# PID_interface_01.net
KiCad netlist of a schematic drawn in EAGLE
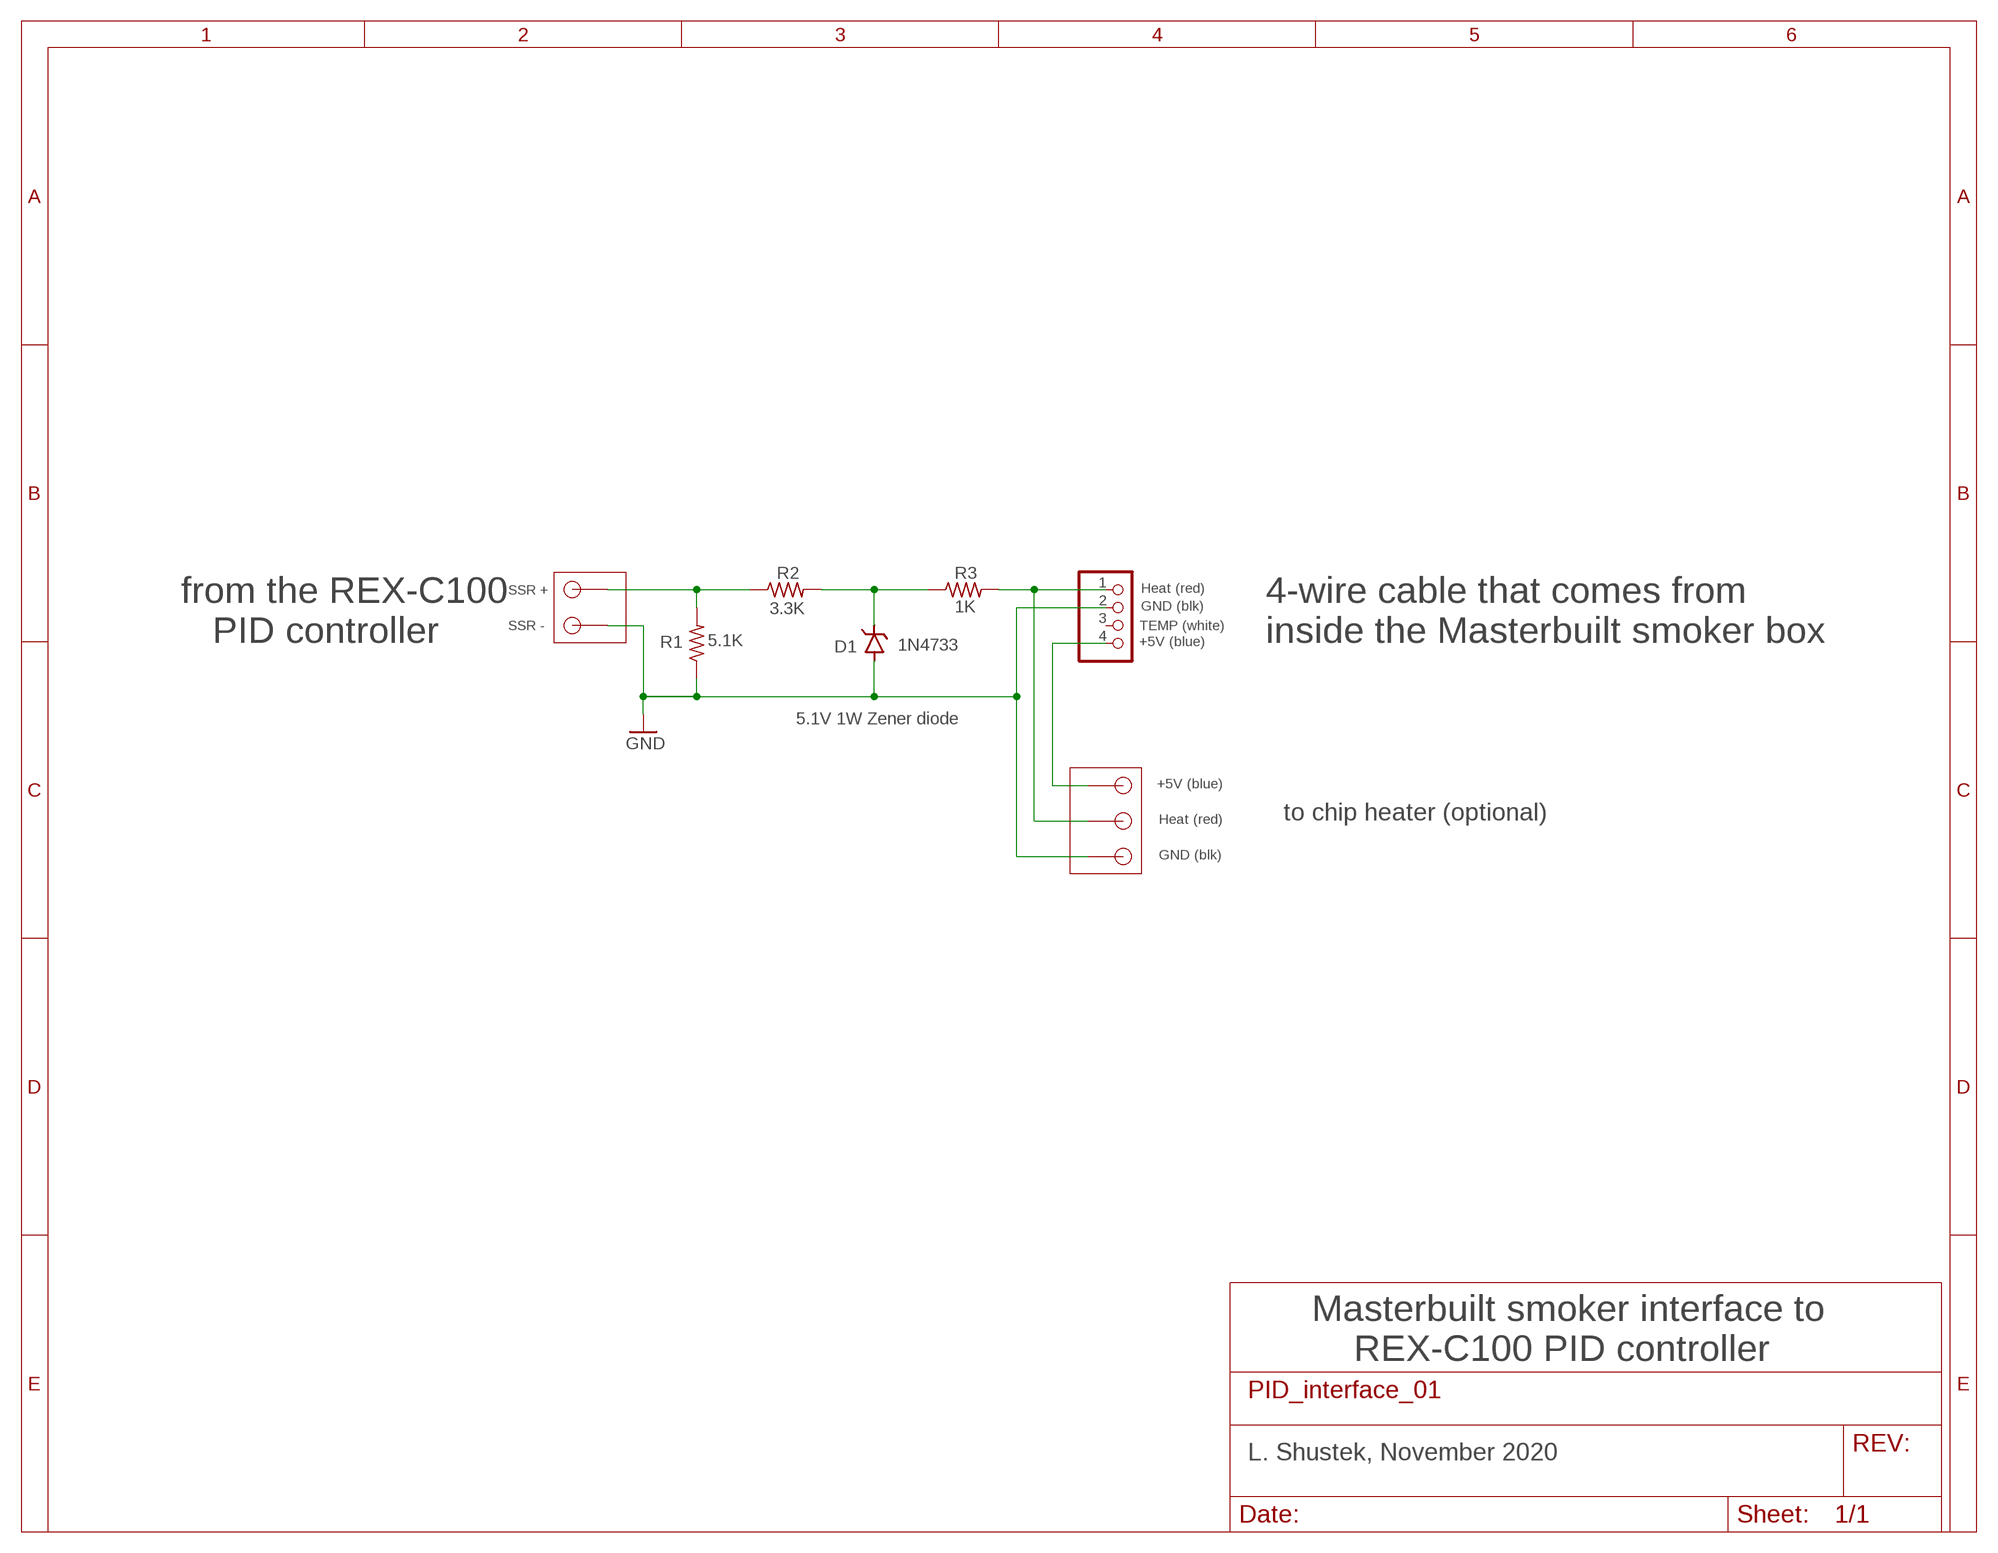
[diagram p0: schematic, sheet 1]

(export (version "E")
  (design (tool "Eeschema 10.0.6"))
  (components
    (comp (ref "D1")
      (value "1N4733")
      (footprint "eagle-import:DO35-10")
      (libsource (lib "eagle-import") (part "DIODE,ZENER1"))
    )
    (comp (ref "JP1")
      (value "PINHD-1X4")
      (footprint "eagle-import:1X04")
      (libsource (lib "eagle-import") (part "PINHD-1X4"))
    )
    (comp (ref "R1")
      (value "5.1K")
      (footprint "eagle-import:0207_10")
      (libsource (lib "eagle-import") (part "R-US_0207/10"))
    )
    (comp (ref "R2")
      (value "3.3K")
      (footprint "eagle-import:0207_10")
      (libsource (lib "eagle-import") (part "R-US_0207/10"))
    )
    (comp (ref "R3")
      (value "1K")
      (footprint "eagle-import:0207_10")
      (libsource (lib "eagle-import") (part "R-US_0207/10"))
    )
    (comp (ref "U$1")
      (value "CONNECTOR-2PINTHIN")
      (footprint "eagle-import:CONNECTOR-2PIN-5MM_THIN")
      (libsource (lib "eagle-import") (part "CONNECTOR-2PINTHIN"))
    )
    (comp (ref "U$2")
      (value "CONNECTOR-3PIN")
      (footprint "eagle-import:CONNECTOR-3PIN-5MM_THIN")
      (libsource (lib "eagle-import") (part "CONNECTOR-3PIN"))
    )
  )
  (nets
    (net (code "1") (name "GND") (class "Default")
      (node (ref "D1") (pin "A") (pinfunction "A_A") (pintype "passive"))
      (node (ref "JP1") (pin "2") (pinfunction "2_2") (pintype "passive"))
      (node (ref "R1") (pin "1") (pinfunction "1_1") (pintype "passive"))
      (node (ref "U$1") (pin "P$1") (pinfunction "P$1_P$1") (pintype "bidirectional"))
      (node (ref "U$2") (pin "P$3") (pinfunction "P$3_P$3") (pintype "bidirectional"))
    )
    (net (code "2") (name "Net-(D1-PadC)") (class "Default")
      (node (ref "D1") (pin "C") (pinfunction "C_C") (pintype "passive"))
      (node (ref "R2") (pin "2") (pinfunction "2_2") (pintype "passive"))
      (node (ref "R3") (pin "1") (pinfunction "1_1") (pintype "passive"))
    )
    (net (code "3") (name "Net-(JP1-Pad1)") (class "Default")
      (node (ref "JP1") (pin "1") (pinfunction "1_1") (pintype "passive"))
      (node (ref "R3") (pin "2") (pinfunction "2_2") (pintype "passive"))
      (node (ref "U$2") (pin "P$2") (pinfunction "P$2_P$2") (pintype "bidirectional"))
    )
    (net (code "4") (name "Net-(JP1-Pad4)") (class "Default")
      (node (ref "JP1") (pin "4") (pinfunction "4_4") (pintype "passive"))
      (node (ref "U$2") (pin "P$1") (pinfunction "P$1_P$1") (pintype "bidirectional"))
    )
    (net (code "5") (name "Net-(R1-Pad2)") (class "Default")
      (node (ref "R1") (pin "2") (pinfunction "2_2") (pintype "passive"))
      (node (ref "R2") (pin "1") (pinfunction "1_1") (pintype "passive"))
      (node (ref "U$1") (pin "P$2") (pinfunction "P$2_P$2") (pintype "bidirectional"))
    )
    (net (code "6") (name "unconnected-(JP1-Pad3)") (class "Default")
      (node (ref "JP1") (pin "3") (pinfunction "3_3") (pintype "passive"))
    )
  )
)
